# Wireless.net
KiCad netlist of a schematic drawn in Altium Designer
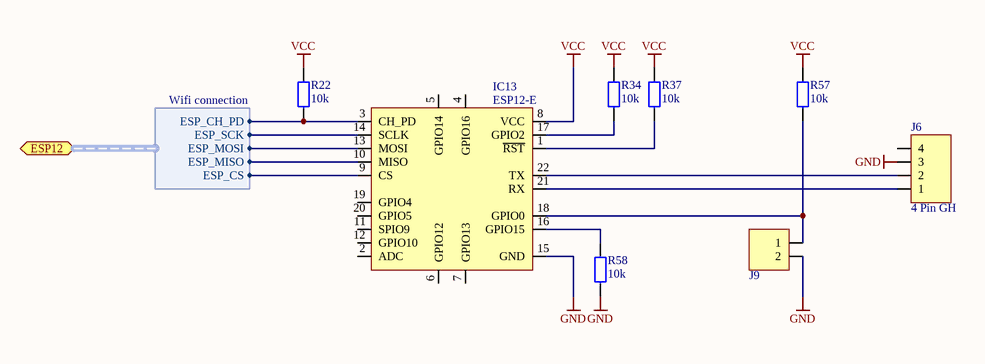
[diagram p0: Wireless.SchDoc]

(export (version "E")
  (design (tool "Eeschema 10.0.6"))
  (components
    (comp (ref "IC13")
      (value "ESP12-E")
      (footprint "ESP8266 ESP-12-E")
      (description "Wifi module, esp12-e, based on ESP8266 chip")
      (libsource (lib "uC") (part "ESP-12E"))
    )
    (comp (ref "J6")
      (value "4 Pin GH")
      (footprint "BM04B")
      (description "Złącze GH, męskie, proste, 4 piny, SMD")
      (libsource (lib "Connectors") (part "4 Pin GH"))
    )
    (comp (ref "J9")
      (value "2 pin")
      (footprint "HDR 1x2 2.54")
      (description "2 pin header, male")
      (libsource (lib "Connectors") (part "2 pin"))
    )
    (comp (ref "R22")
      (value "10k")
      (footprint "RES 0603")
      (description "SMDResistor")
      (libsource (lib "Passive") (part "Resistor"))
    )
    (comp (ref "R34")
      (value "10k")
      (footprint "RES 0603")
      (description "SMDResistor")
      (libsource (lib "Passive") (part "Resistor"))
    )
    (comp (ref "R37")
      (value "10k")
      (footprint "RES 0603")
      (description "SMDResistor")
      (libsource (lib "Passive") (part "Resistor"))
    )
    (comp (ref "R57")
      (value "10k")
      (footprint "RES 0603")
      (description "SMDResistor")
      (libsource (lib "Passive") (part "Resistor"))
    )
    (comp (ref "R58")
      (value "10k")
      (footprint "RES 0603")
      (description "SMDResistor")
      (libsource (lib "Passive") (part "Resistor"))
    )
  )
  (nets
    (net (code "3") (name "/ESP_CH_PD") (class "Default")
      (node (ref "IC13") (pin "3") (pinfunction "CH_PD_3") (pintype "passive"))
      (node (ref "R22") (pin "1") (pinfunction "1_1") (pintype "passive"))
    )
    (net (code "4") (name "/ESP_CS") (class "Default")
      (node (ref "IC13") (pin "9") (pinfunction "CS_9") (pintype "passive"))
    )
    (net (code "5") (name "/ESP_MISO") (class "Default")
      (node (ref "IC13") (pin "10") (pinfunction "MISO_10") (pintype "passive"))
    )
    (net (code "6") (name "/ESP_MOSI") (class "Default")
      (node (ref "IC13") (pin "13") (pinfunction "MOSI_13") (pintype "passive"))
    )
    (net (code "7") (name "/ESP_SCK") (class "Default")
      (node (ref "IC13") (pin "14") (pinfunction "SCLK_14") (pintype "passive"))
    )
    (net (code "9") (name "GND") (class "Default")
      (node (ref "IC13") (pin "15") (pinfunction "GND_15") (pintype "passive"))
      (node (ref "J6") (pin "3") (pinfunction "3_3") (pintype "passive"))
      (node (ref "J9") (pin "2") (pinfunction "2_2") (pintype "passive"))
      (node (ref "R58") (pin "1") (pinfunction "1_1") (pintype "passive"))
    )
    (net (code "10") (name "Net-(IC13-GPIO0)") (class "Default")
      (node (ref "IC13") (pin "18") (pinfunction "GPIO0_18") (pintype "passive"))
      (node (ref "J9") (pin "1") (pinfunction "1_1") (pintype "passive"))
      (node (ref "R57") (pin "1") (pinfunction "1_1") (pintype "passive"))
    )
    (net (code "11") (name "Net-(IC13-GPIO2)") (class "Default")
      (node (ref "IC13") (pin "17") (pinfunction "GPIO2_17") (pintype "passive"))
      (node (ref "R34") (pin "1") (pinfunction "1_1") (pintype "passive"))
    )
    (net (code "12") (name "Net-(IC13-GPIO15)") (class "Default")
      (node (ref "IC13") (pin "16") (pinfunction "GPIO15_16") (pintype "passive"))
      (node (ref "R58") (pin "2") (pinfunction "2_2") (pintype "passive"))
    )
    (net (code "13") (name "Net-(IC13-RX)") (class "Default")
      (node (ref "IC13") (pin "21") (pinfunction "RX_21") (pintype "passive"))
      (node (ref "J6") (pin "1") (pinfunction "1_1") (pintype "passive"))
    )
    (net (code "14") (name "Net-(IC13-TX)") (class "Default")
      (node (ref "IC13") (pin "22") (pinfunction "TX_22") (pintype "passive"))
      (node (ref "J6") (pin "2") (pinfunction "2_2") (pintype "passive"))
    )
    (net (code "15") (name "Net-(IC13-~{RST})") (class "Default")
      (node (ref "IC13") (pin "1") (pinfunction "~{RST}_1") (pintype "passive"))
      (node (ref "R37") (pin "1") (pinfunction "1_1") (pintype "passive"))
    )
    (net (code "16") (name "VCC") (class "Default")
      (node (ref "IC13") (pin "8") (pinfunction "VCC_8") (pintype "passive"))
      (node (ref "R22") (pin "2") (pinfunction "2_2") (pintype "passive"))
      (node (ref "R34") (pin "2") (pinfunction "2_2") (pintype "passive"))
      (node (ref "R37") (pin "2") (pinfunction "2_2") (pintype "passive"))
      (node (ref "R57") (pin "2") (pinfunction "2_2") (pintype "passive"))
    )
    (net (code "17") (name "unconnected-(IC13-ADC-Pad2)") (class "Default")
      (node (ref "IC13") (pin "2") (pinfunction "ADC_2") (pintype "passive"))
    )
    (net (code "18") (name "unconnected-(IC13-GPIO4-Pad19)") (class "Default")
      (node (ref "IC13") (pin "19") (pinfunction "GPIO4_19") (pintype "passive"))
    )
    (net (code "19") (name "unconnected-(IC13-GPIO5-Pad20)") (class "Default")
      (node (ref "IC13") (pin "20") (pinfunction "GPIO5_20") (pintype "passive"))
    )
    (net (code "20") (name "unconnected-(IC13-GPIO10-Pad12)") (class "Default")
      (node (ref "IC13") (pin "12") (pinfunction "GPIO10_12") (pintype "passive"))
    )
    (net (code "21") (name "unconnected-(IC13-GPIO12-Pad6)") (class "Default")
      (node (ref "IC13") (pin "6") (pinfunction "GPIO12_6") (pintype "passive"))
    )
    (net (code "22") (name "unconnected-(IC13-GPIO13-Pad7)") (class "Default")
      (node (ref "IC13") (pin "7") (pinfunction "GPIO13_7") (pintype "passive"))
    )
    (net (code "23") (name "unconnected-(IC13-GPIO14-Pad5)") (class "Default")
      (node (ref "IC13") (pin "5") (pinfunction "GPIO14_5") (pintype "passive"))
    )
    (net (code "24") (name "unconnected-(IC13-GPIO16-Pad4)") (class "Default")
      (node (ref "IC13") (pin "4") (pinfunction "GPIO16_4") (pintype "passive"))
    )
    (net (code "25") (name "unconnected-(IC13-SPIO9-Pad11)") (class "Default")
      (node (ref "IC13") (pin "11") (pinfunction "SPIO9_11") (pintype "passive"))
    )
    (net (code "26") (name "unconnected-(J6-Pad4)") (class "Default")
      (node (ref "J6") (pin "4") (pinfunction "4_4") (pintype "passive"))
    )
  )
)
